# Sheet1.net
KiCad netlist of a schematic drawn in Altium Designer
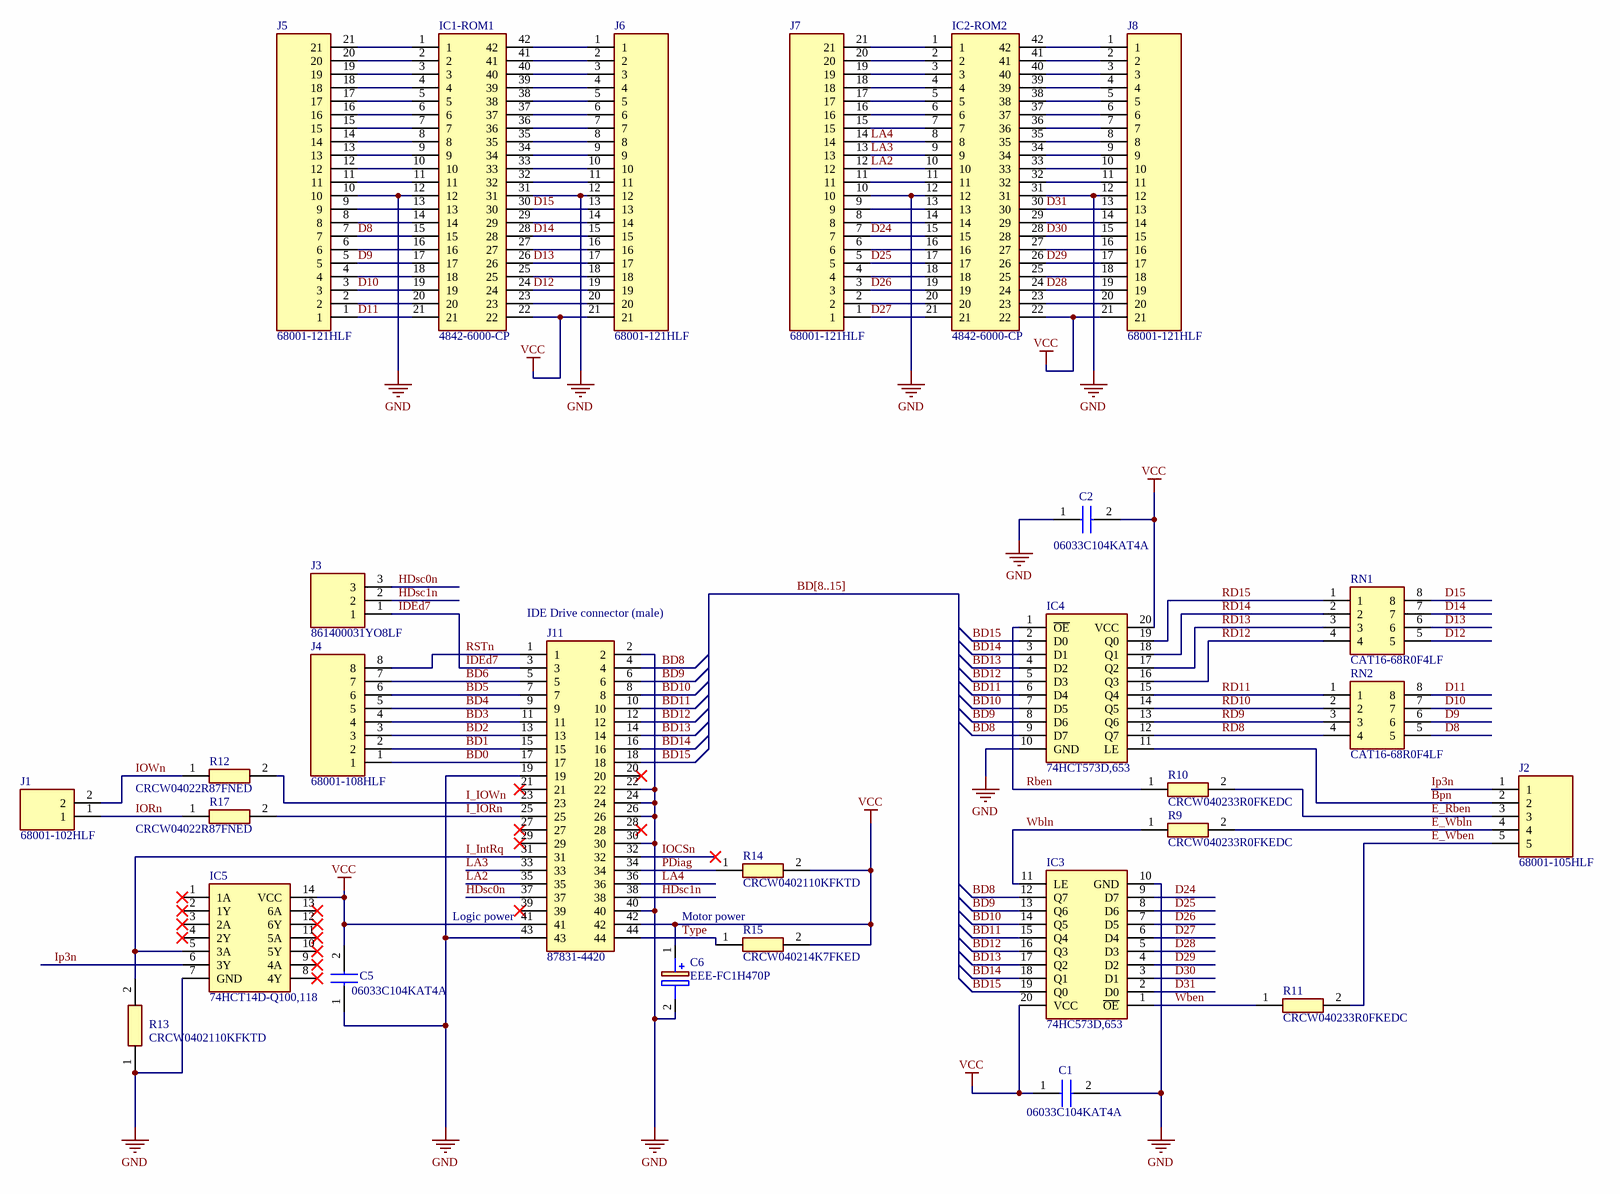
[diagram p0: Sheet1.SchDoc]

(export (version "E")
  (design (tool "Eeschema 10.0.6"))
  (components
    (comp (ref "C1")
      (value "06033C104KAT4A")
      (footprint "SamacSys:CAPC1608X90N")
      (description "Capacitor")
      (fields (field (name "MOUSER PART NUMBER") "581-06033C104KAT4A"))
      (libsource (lib "*") (part "06033C104KAT4A"))
    )
    (comp (ref "C2")
      (value "06033C104KAT4A")
      (footprint "SamacSys:CAPC1608X90N")
      (description "Capacitor")
      (fields (field (name "MOUSER PART NUMBER") "581-06033C104KAT4A"))
      (libsource (lib "*") (part "06033C104KAT4A"))
    )
    (comp (ref "C5")
      (value "06033C104KAT4A")
      (footprint "SamacSys:CAPC1608X90N")
      (description "Capacitor")
      (fields (field (name "MOUSER PART NUMBER") "581-06033C104KAT4A"))
      (libsource (lib "*") (part "06033C104KAT4A"))
    )
    (comp (ref "C6")
      (value "EEE-FC1H470P")
      (footprint "SamacSys:EEEFK1V331P")
      (description "Capacitor Polarised")
      (fields (field (name "MOUSER PART NUMBER") "667-EEE-FC1H470P"))
      (libsource (lib "*") (part "EEE-FC1H470P"))
    )
    (comp (ref "IC1-ROM1")
      (value "4842-6000-CP")
      (footprint "SamacSys:48426000CP")
      (description "Connector")
      (fields (field (name "MOUSER PART NUMBER") "517-4842-6000-CP"))
      (libsource (lib "*") (part "4842-6000-CP"))
    )
    (comp (ref "IC2-ROM2")
      (value "4842-6000-CP")
      (footprint "SamacSys:48426000CP")
      (description "Connector")
      (fields (field (name "MOUSER PART NUMBER") "517-4842-6000-CP"))
      (libsource (lib "*") (part "4842-6000-CP"))
    )
    (comp (ref "IC3")
      (value "74HC573D,653")
      (footprint "SamacSys:SOIC127P1032X265-20N")
      (description "Integrated Circuit")
      (fields (field (name "MOUSER PART NUMBER") "771-74HC573D-T"))
      (libsource (lib "*") (part "74HC573D,653"))
    )
    (comp (ref "IC4")
      (value "74HCT573D,653")
      (footprint "SamacSys:SOIC127P1032X265-20N")
      (description "Integrated Circuit")
      (fields (field (name "MOUSER PART NUMBER") "771-HCT573D653"))
      (libsource (lib "*") (part "74HCT573D,653"))
    )
    (comp (ref "IC5")
      (value "74HCT14D-Q100,118")
      (footprint "SamacSys:SOIC127P600X175-14N")
      (description "Integrated Circuit")
      (fields (field (name "MOUSER PART NUMBER") "771-74HCT14D-Q100118"))
      (libsource (lib "*") (part "74HCT14D-Q100,118"))
    )
    (comp (ref "J1")
      (value "68001-102HLF")
      (footprint "SamacSys:HDRV2W67P0X254_1X2_508X241X858P")
      (description "Connector")
      (fields (field (name "MOUSER PART NUMBER") "649-68001-102HLF"))
      (libsource (lib "*") (part "68001-102HLF"))
    )
    (comp (ref "J2")
      (value "68001-105HLF")
      (footprint "SamacSys:HDRV5W90P0X254_1X5_1270X241X1143P")
      (description "Connector")
      (fields (field (name "MOUSER PART NUMBER") "649-68001-105HLF"))
      (libsource (lib "*") (part "68001-105HLF"))
    )
    (comp (ref "J3")
      (value "861400031YO8LF")
      (footprint "SamacSys:HDRV3W63P0X254_1X3_762X254X980P")
      (description "Connector")
      (fields (field (name "MOUSER PART NUMBER") "649-861400031YO8LF"))
      (libsource (lib "*") (part "861400031YO8LF"))
    )
    (comp (ref "J4")
      (value "68001-108HLF")
      (footprint "SamacSys:HDRV8W90P0X254_1X8_2032X241X1143P")
      (description "Connector")
      (fields (field (name "MOUSER PART NUMBER") "649-68001-108HLF"))
      (libsource (lib "*") (part "68001-108HLF"))
    )
    (comp (ref "J5")
      (value "68001-121HLF")
      (footprint "SamacSys:HDRV21W67P0X254_1X21_5334X241X858P")
      (description "Connector")
      (fields (field (name "MOUSER PART NUMBER") "649-68001-121HLF"))
      (libsource (lib "*") (part "68001-121HLF"))
    )
    (comp (ref "J6")
      (value "68001-121HLF")
      (footprint "SamacSys:HDRV21W67P0X254_1X21_5334X241X858P")
      (description "Connector")
      (fields (field (name "MOUSER PART NUMBER") "649-68001-121HLF"))
      (libsource (lib "") (part "68001-121HLF_1"))
    )
    (comp (ref "J7")
      (value "68001-121HLF")
      (footprint "SamacSys:HDRV21W67P0X254_1X21_5334X241X858P")
      (description "Connector")
      (fields (field (name "MOUSER PART NUMBER") "649-68001-121HLF"))
      (libsource (lib "*") (part "68001-121HLF"))
    )
    (comp (ref "J8")
      (value "68001-121HLF")
      (footprint "SamacSys:HDRV21W67P0X254_1X21_5334X241X858P")
      (description "Connector")
      (fields (field (name "MOUSER PART NUMBER") "649-68001-121HLF"))
      (libsource (lib "") (part "68001-121HLF_1"))
    )
    (comp (ref "J11")
      (value "87831-4420")
      (footprint "SamacSys:SHDR44W55P200_2X22_4665X630X640P")
      (description "Connector")
      (fields (field (name "MOUSER PART NUMBER") "538-87831-4420"))
      (libsource (lib "*") (part "87831-4420"))
    )
    (comp (ref "R9")
      (value "CRCW040233R0FKEDC")
      (footprint "SamacSys:RESC1005X35N")
      (description "Resistor")
      (fields (field (name "MOUSER PART NUMBER") "71-CRCW040233R0FKEDC"))
      (libsource (lib "*") (part "CRCW040233R0FKEDC"))
    )
    (comp (ref "R10")
      (value "CRCW040233R0FKEDC")
      (footprint "SamacSys:RESC1005X35N")
      (description "Resistor")
      (fields (field (name "MOUSER PART NUMBER") "71-CRCW040233R0FKEDC"))
      (libsource (lib "*") (part "CRCW040233R0FKEDC"))
    )
    (comp (ref "R11")
      (value "CRCW040233R0FKEDC")
      (footprint "SamacSys:RESC1005X35N")
      (description "Resistor")
      (fields (field (name "MOUSER PART NUMBER") "71-CRCW040233R0FKEDC"))
      (libsource (lib "*") (part "CRCW040233R0FKEDC"))
    )
    (comp (ref "R12")
      (value "CRCW04022R87FNED")
      (footprint "SamacSys:RESC1005X40N")
      (description "Resistor")
      (fields (field (name "MOUSER PART NUMBER") "71-CRCW04022R87FNED"))
      (libsource (lib "*") (part "CRCW04022R87FNED"))
    )
    (comp (ref "R13")
      (value "CRCW0402110KFKTD")
      (footprint "SamacSys:RESC1005X40N")
      (description "Resistor")
      (fields (field (name "MOUSER PART NUMBER") "71-CRCW0402-110K"))
      (libsource (lib "") (part "CRCW0402110KFKTD_1"))
    )
    (comp (ref "R14")
      (value "CRCW0402110KFKTD")
      (footprint "SamacSys:RESC1005X40N")
      (description "Resistor")
      (fields (field (name "MOUSER PART NUMBER") "71-CRCW0402-110K"))
      (libsource (lib "*") (part "CRCW0402110KFKTD"))
    )
    (comp (ref "R15")
      (value "CRCW040214K7FKED")
      (footprint "SamacSys:RESC1005X40N")
      (description "Resistor")
      (fields (field (name "MOUSER PART NUMBER") "71-CRCW0402-14.7K-E3"))
      (libsource (lib "*") (part "CRCW040214K7FKED"))
    )
    (comp (ref "R17")
      (value "CRCW04022R87FNED")
      (footprint "SamacSys:RESC1005X40N")
      (description "Resistor")
      (fields (field (name "MOUSER PART NUMBER") "71-CRCW04022R87FNED"))
      (libsource (lib "*") (part "CRCW04022R87FNED"))
    )
    (comp (ref "RN1")
      (value "CAT16-68R0F4LF")
      (footprint "SamacSys:CAT1668R0F4LF")
      (description "Resistor Network")
      (fields (field (name "MOUSER PART NUMBER") "652-CAT16-68R0F4LF"))
      (libsource (lib "*") (part "CAT16-68R0F4LF"))
    )
    (comp (ref "RN2")
      (value "CAT16-68R0F4LF")
      (footprint "SamacSys:CAT1668R0F4LF")
      (description "Resistor Network")
      (fields (field (name "MOUSER PART NUMBER") "652-CAT16-68R0F4LF"))
      (libsource (lib "*") (part "CAT16-68R0F4LF"))
    )
  )
  (nets
    (net (code "1") (name "/BD0") (class "Default")
      (node (ref "J11") (pin "17") (pinfunction "17_17") (pintype "passive"))
      (node (ref "J4") (pin "1") (pinfunction "1_1") (pintype "passive"))
    )
    (net (code "2") (name "/BD1") (class "Default")
      (node (ref "J11") (pin "15") (pinfunction "15_15") (pintype "passive"))
      (node (ref "J4") (pin "2") (pinfunction "2_2") (pintype "passive"))
    )
    (net (code "3") (name "/BD2") (class "Default")
      (node (ref "J11") (pin "13") (pinfunction "13_13") (pintype "passive"))
      (node (ref "J4") (pin "3") (pinfunction "3_3") (pintype "passive"))
    )
    (net (code "4") (name "/BD3") (class "Default")
      (node (ref "J11") (pin "11") (pinfunction "11_11") (pintype "passive"))
      (node (ref "J4") (pin "4") (pinfunction "4_4") (pintype "passive"))
    )
    (net (code "5") (name "/BD4") (class "Default")
      (node (ref "J11") (pin "9") (pinfunction "9_9") (pintype "passive"))
      (node (ref "J4") (pin "5") (pinfunction "5_5") (pintype "passive"))
    )
    (net (code "6") (name "/BD5") (class "Default")
      (node (ref "J11") (pin "7") (pinfunction "7_7") (pintype "passive"))
      (node (ref "J4") (pin "6") (pinfunction "6_6") (pintype "passive"))
    )
    (net (code "7") (name "/BD6") (class "Default")
      (node (ref "J11") (pin "5") (pinfunction "5_5") (pintype "passive"))
      (node (ref "J4") (pin "7") (pinfunction "7_7") (pintype "passive"))
    )
    (net (code "8") (name "/BD8") (class "Default")
      (node (ref "IC3") (pin "12") (pinfunction "Q7_12") (pintype "passive"))
      (node (ref "IC4") (pin "9") (pinfunction "D7_9") (pintype "passive"))
      (node (ref "J11") (pin "4") (pinfunction "4_4") (pintype "passive"))
    )
    (net (code "9") (name "/BD9") (class "Default")
      (node (ref "IC3") (pin "13") (pinfunction "Q6_13") (pintype "passive"))
      (node (ref "IC4") (pin "8") (pinfunction "D6_8") (pintype "passive"))
      (node (ref "J11") (pin "6") (pinfunction "6_6") (pintype "passive"))
    )
    (net (code "10") (name "/BD10") (class "Default")
      (node (ref "IC3") (pin "14") (pinfunction "Q5_14") (pintype "passive"))
      (node (ref "IC4") (pin "7") (pinfunction "D5_7") (pintype "passive"))
      (node (ref "J11") (pin "8") (pinfunction "8_8") (pintype "passive"))
    )
    (net (code "11") (name "/BD11") (class "Default")
      (node (ref "IC3") (pin "15") (pinfunction "Q4_15") (pintype "passive"))
      (node (ref "IC4") (pin "6") (pinfunction "D4_6") (pintype "passive"))
      (node (ref "J11") (pin "10") (pinfunction "10_10") (pintype "passive"))
    )
    (net (code "12") (name "/BD12") (class "Default")
      (node (ref "IC3") (pin "16") (pinfunction "Q3_16") (pintype "passive"))
      (node (ref "IC4") (pin "5") (pinfunction "D3_5") (pintype "passive"))
      (node (ref "J11") (pin "12") (pinfunction "12_12") (pintype "passive"))
    )
    (net (code "13") (name "/BD13") (class "Default")
      (node (ref "IC3") (pin "17") (pinfunction "Q2_17") (pintype "passive"))
      (node (ref "IC4") (pin "4") (pinfunction "D2_4") (pintype "passive"))
      (node (ref "J11") (pin "14") (pinfunction "14_14") (pintype "passive"))
    )
    (net (code "14") (name "/BD14") (class "Default")
      (node (ref "IC3") (pin "18") (pinfunction "Q1_18") (pintype "passive"))
      (node (ref "IC4") (pin "3") (pinfunction "D1_3") (pintype "passive"))
      (node (ref "J11") (pin "16") (pinfunction "16_16") (pintype "passive"))
    )
    (net (code "15") (name "/BD15") (class "Default")
      (node (ref "IC3") (pin "19") (pinfunction "Q0_19") (pintype "passive"))
      (node (ref "IC4") (pin "2") (pinfunction "D0_2") (pintype "passive"))
      (node (ref "J11") (pin "18") (pinfunction "18_18") (pintype "passive"))
    )
    (net (code "17") (name "/Bpn") (class "Default")
      (node (ref "IC4") (pin "11") (pinfunction "LE_11") (pintype "passive"))
      (node (ref "J2") (pin "2") (pinfunction "2_2") (pintype "passive"))
    )
    (net (code "18") (name "/D8") (class "Default")
      (node (ref "IC1-ROM1") (pin "15") (pinfunction "15_15") (pintype "passive"))
      (node (ref "J5") (pin "7") (pinfunction "7_7") (pintype "passive"))
      (node (ref "RN2") (pin "5") (pinfunction "5_5") (pintype "passive"))
    )
    (net (code "19") (name "/D9") (class "Default")
      (node (ref "IC1-ROM1") (pin "17") (pinfunction "17_17") (pintype "passive"))
      (node (ref "J5") (pin "5") (pinfunction "5_5") (pintype "passive"))
      (node (ref "RN2") (pin "6") (pinfunction "6_6") (pintype "passive"))
    )
    (net (code "20") (name "/D10") (class "Default")
      (node (ref "IC1-ROM1") (pin "19") (pinfunction "19_19") (pintype "passive"))
      (node (ref "J5") (pin "3") (pinfunction "3_3") (pintype "passive"))
      (node (ref "RN2") (pin "7") (pinfunction "7_7") (pintype "passive"))
    )
    (net (code "21") (name "/D11") (class "Default")
      (node (ref "IC1-ROM1") (pin "21") (pinfunction "21_21") (pintype "passive"))
      (node (ref "J5") (pin "1") (pinfunction "1_1") (pintype "passive"))
      (node (ref "RN2") (pin "8") (pinfunction "8_8") (pintype "passive"))
    )
    (net (code "22") (name "/D12") (class "Default")
      (node (ref "IC1-ROM1") (pin "24") (pinfunction "24_24") (pintype "passive"))
      (node (ref "J6") (pin "19") (pinfunction "19_19") (pintype "passive"))
      (node (ref "RN1") (pin "5") (pinfunction "5_5") (pintype "passive"))
    )
    (net (code "23") (name "/D13") (class "Default")
      (node (ref "IC1-ROM1") (pin "26") (pinfunction "26_26") (pintype "passive"))
      (node (ref "J6") (pin "17") (pinfunction "17_17") (pintype "passive"))
      (node (ref "RN1") (pin "6") (pinfunction "6_6") (pintype "passive"))
    )
    (net (code "24") (name "/D14") (class "Default")
      (node (ref "IC1-ROM1") (pin "28") (pinfunction "28_28") (pintype "passive"))
      (node (ref "J6") (pin "15") (pinfunction "15_15") (pintype "passive"))
      (node (ref "RN1") (pin "7") (pinfunction "7_7") (pintype "passive"))
    )
    (net (code "25") (name "/D15") (class "Default")
      (node (ref "IC1-ROM1") (pin "30") (pinfunction "30_30") (pintype "passive"))
      (node (ref "J6") (pin "13") (pinfunction "13_13") (pintype "passive"))
      (node (ref "RN1") (pin "8") (pinfunction "8_8") (pintype "passive"))
    )
    (net (code "26") (name "/D24") (class "Default")
      (node (ref "IC2-ROM2") (pin "15") (pinfunction "15_15") (pintype "passive"))
      (node (ref "IC3") (pin "9") (pinfunction "D7_9") (pintype "passive"))
      (node (ref "J7") (pin "7") (pinfunction "7_7") (pintype "passive"))
    )
    (net (code "27") (name "/D25") (class "Default")
      (node (ref "IC2-ROM2") (pin "17") (pinfunction "17_17") (pintype "passive"))
      (node (ref "IC3") (pin "8") (pinfunction "D6_8") (pintype "passive"))
      (node (ref "J7") (pin "5") (pinfunction "5_5") (pintype "passive"))
    )
    (net (code "28") (name "/D26") (class "Default")
      (node (ref "IC2-ROM2") (pin "19") (pinfunction "19_19") (pintype "passive"))
      (node (ref "IC3") (pin "7") (pinfunction "D5_7") (pintype "passive"))
      (node (ref "J7") (pin "3") (pinfunction "3_3") (pintype "passive"))
    )
    (net (code "29") (name "/D27") (class "Default")
      (node (ref "IC2-ROM2") (pin "21") (pinfunction "21_21") (pintype "passive"))
      (node (ref "IC3") (pin "6") (pinfunction "D4_6") (pintype "passive"))
      (node (ref "J7") (pin "1") (pinfunction "1_1") (pintype "passive"))
    )
    (net (code "30") (name "/D28") (class "Default")
      (node (ref "IC2-ROM2") (pin "24") (pinfunction "24_24") (pintype "passive"))
      (node (ref "IC3") (pin "5") (pinfunction "D3_5") (pintype "passive"))
      (node (ref "J8") (pin "19") (pinfunction "19_19") (pintype "passive"))
    )
    (net (code "31") (name "/D29") (class "Default")
      (node (ref "IC2-ROM2") (pin "26") (pinfunction "26_26") (pintype "passive"))
      (node (ref "IC3") (pin "4") (pinfunction "D2_4") (pintype "passive"))
      (node (ref "J8") (pin "17") (pinfunction "17_17") (pintype "passive"))
    )
    (net (code "32") (name "/D30") (class "Default")
      (node (ref "IC2-ROM2") (pin "28") (pinfunction "28_28") (pintype "passive"))
      (node (ref "IC3") (pin "3") (pinfunction "D1_3") (pintype "passive"))
      (node (ref "J8") (pin "15") (pinfunction "15_15") (pintype "passive"))
    )
    (net (code "33") (name "/D31") (class "Default")
      (node (ref "IC2-ROM2") (pin "30") (pinfunction "30_30") (pintype "passive"))
      (node (ref "IC3") (pin "2") (pinfunction "D0_2") (pintype "passive"))
      (node (ref "J8") (pin "13") (pinfunction "13_13") (pintype "passive"))
    )
    (net (code "34") (name "/E_Rben") (class "Default")
      (node (ref "J2") (pin "3") (pinfunction "3_3") (pintype "passive"))
      (node (ref "R10") (pin "2") (pinfunction "2_2") (pintype "passive"))
    )
    (net (code "35") (name "/E_Wben") (class "Default")
      (node (ref "J2") (pin "5") (pinfunction "5_5") (pintype "passive"))
      (node (ref "R11") (pin "2") (pinfunction "2_2") (pintype "passive"))
    )
    (net (code "36") (name "/E_Wbln") (class "Default")
      (node (ref "J2") (pin "4") (pinfunction "4_4") (pintype "passive"))
      (node (ref "R9") (pin "2") (pinfunction "2_2") (pintype "passive"))
    )
    (net (code "37") (name "/HDsc0n") (class "Default")
      (node (ref "J11") (pin "37") (pinfunction "37_37") (pintype "passive"))
      (node (ref "J3") (pin "3") (pinfunction "3_3") (pintype "passive"))
    )
    (net (code "38") (name "/HDsc1n") (class "Default")
      (node (ref "J11") (pin "38") (pinfunction "38_38") (pintype "passive"))
      (node (ref "J3") (pin "2") (pinfunction "2_2") (pintype "passive"))
    )
    (net (code "39") (name "/IDEd7") (class "Default")
      (node (ref "J11") (pin "3") (pinfunction "3_3") (pintype "passive"))
      (node (ref "J3") (pin "1") (pinfunction "1_1") (pintype "passive"))
    )
    (net (code "40") (name "/IOCSn") (class "Default")
      (node (ref "J11") (pin "32") (pinfunction "32_32") (pintype "passive+no_connect"))
    )
    (net (code "41") (name "/IORn") (class "Default")
      (node (ref "J1") (pin "1") (pinfunction "1_1") (pintype "passive"))
      (node (ref "R17") (pin "1") (pinfunction "1_1") (pintype "passive"))
    )
    (net (code "42") (name "/IOWn") (class "Default")
      (node (ref "J1") (pin "2") (pinfunction "2_2") (pintype "passive"))
      (node (ref "R12") (pin "1") (pinfunction "1_1") (pintype "passive"))
    )
    (net (code "43") (name "/I_IORn") (class "Default")
      (node (ref "J11") (pin "25") (pinfunction "25_25") (pintype "passive"))
      (node (ref "R17") (pin "2") (pinfunction "2_2") (pintype "passive"))
    )
    (net (code "44") (name "/I_IOWn") (class "Default")
      (node (ref "J11") (pin "23") (pinfunction "23_23") (pintype "passive"))
      (node (ref "R12") (pin "2") (pinfunction "2_2") (pintype "passive"))
    )
    (net (code "45") (name "/I_IntRq") (class "Default")
      (node (ref "IC5") (pin "5") (pinfunction "3A_5") (pintype "passive"))
      (node (ref "J11") (pin "31") (pinfunction "31_31") (pintype "passive"))
      (node (ref "R13") (pin "2") (pinfunction "2_2") (pintype "passive"))
    )
    (net (code "46") (name "/Ip3n") (class "Default")
      (node (ref "IC5") (pin "6") (pinfunction "3Y_6") (pintype "passive"))
      (node (ref "J2") (pin "1") (pinfunction "1_1") (pintype "passive"))
    )
    (net (code "47") (name "/LA2") (class "Default")
      (node (ref "IC2-ROM2") (pin "10") (pinfunction "10_10") (pintype "passive"))
      (node (ref "J11") (pin "35") (pinfunction "35_35") (pintype "passive"))
      (node (ref "J7") (pin "12") (pinfunction "12_12") (pintype "passive"))
    )
    (net (code "48") (name "/LA3") (class "Default")
      (node (ref "IC2-ROM2") (pin "9") (pinfunction "9_9") (pintype "passive"))
      (node (ref "J11") (pin "33") (pinfunction "33_33") (pintype "passive"))
      (node (ref "J7") (pin "13") (pinfunction "13_13") (pintype "passive"))
    )
    (net (code "49") (name "/LA4") (class "Default")
      (node (ref "IC2-ROM2") (pin "8") (pinfunction "8_8") (pintype "passive"))
      (node (ref "J11") (pin "36") (pinfunction "36_36") (pintype "passive"))
      (node (ref "J7") (pin "14") (pinfunction "14_14") (pintype "passive"))
    )
    (net (code "50") (name "/PDiag") (class "Default")
      (node (ref "J11") (pin "34") (pinfunction "34_34") (pintype "passive"))
      (node (ref "R14") (pin "1") (pinfunction "1_1") (pintype "passive"))
    )
    (net (code "51") (name "/RD8") (class "Default")
      (node (ref "IC4") (pin "12") (pinfunction "Q7_12") (pintype "passive"))
      (node (ref "RN2") (pin "4") (pinfunction "4_4") (pintype "passive"))
    )
    (net (code "52") (name "/RD9") (class "Default")
      (node (ref "IC4") (pin "13") (pinfunction "Q6_13") (pintype "passive"))
      (node (ref "RN2") (pin "3") (pinfunction "3_3") (pintype "passive"))
    )
    (net (code "53") (name "/RD10") (class "Default")
      (node (ref "IC4") (pin "14") (pinfunction "Q5_14") (pintype "passive"))
      (node (ref "RN2") (pin "2") (pinfunction "2_2") (pintype "passive"))
    )
    (net (code "54") (name "/RD11") (class "Default")
      (node (ref "IC4") (pin "15") (pinfunction "Q4_15") (pintype "passive"))
      (node (ref "RN2") (pin "1") (pinfunction "1_1") (pintype "passive"))
    )
    (net (code "55") (name "/RD12") (class "Default")
      (node (ref "IC4") (pin "16") (pinfunction "Q3_16") (pintype "passive"))
      (node (ref "RN1") (pin "4") (pinfunction "4_4") (pintype "passive"))
    )
    (net (code "56") (name "/RD13") (class "Default")
      (node (ref "IC4") (pin "17") (pinfunction "Q2_17") (pintype "passive"))
      (node (ref "RN1") (pin "3") (pinfunction "3_3") (pintype "passive"))
    )
    (net (code "57") (name "/RD14") (class "Default")
      (node (ref "IC4") (pin "18") (pinfunction "Q1_18") (pintype "passive"))
      (node (ref "RN1") (pin "2") (pinfunction "2_2") (pintype "passive"))
    )
    (net (code "58") (name "/RD15") (class "Default")
      (node (ref "IC4") (pin "19") (pinfunction "Q0_19") (pintype "passive"))
      (node (ref "RN1") (pin "1") (pinfunction "1_1") (pintype "passive"))
    )
    (net (code "59") (name "/RSTn") (class "Default")
      (node (ref "J11") (pin "1") (pinfunction "1_1") (pintype "passive"))
      (node (ref "J4") (pin "8") (pinfunction "8_8") (pintype "passive"))
    )
    (net (code "60") (name "/Rben") (class "Default")
      (node (ref "IC4") (pin "1") (pinfunction "~{OE}_1") (pintype "passive"))
      (node (ref "R10") (pin "1") (pinfunction "1_1") (pintype "passive"))
    )
    (net (code "61") (name "/Type") (class "Default")
      (node (ref "J11") (pin "44") (pinfunction "44_44") (pintype "passive"))
      (node (ref "R15") (pin "1") (pinfunction "1_1") (pintype "passive"))
    )
    (net (code "62") (name "/Wben") (class "Default")
      (node (ref "IC3") (pin "1") (pinfunction "~{OE}_1") (pintype "passive"))
      (node (ref "R11") (pin "1") (pinfunction "1_1") (pintype "passive"))
    )
    (net (code "63") (name "/Wbln") (class "Default")
      (node (ref "IC3") (pin "11") (pinfunction "LE_11") (pintype "passive"))
      (node (ref "R9") (pin "1") (pinfunction "1_1") (pintype "passive"))
    )
    (net (code "64") (name "GND") (class "Default")
      (node (ref "C1") (pin "2") (pinfunction "2_2") (pintype "passive"))
      (node (ref "C2") (pin "1") (pinfunction "1_1") (pintype "passive"))
      (node (ref "C5") (pin "1") (pinfunction "1_1") (pintype "passive"))
      (node (ref "C6") (pin "2") (pinfunction "-_2") (pintype "passive"))
      (node (ref "IC1-ROM1") (pin "12") (pinfunction "12_12") (pintype "passive"))
      (node (ref "IC1-ROM1") (pin "31") (pinfunction "31_31") (pintype "passive"))
      (node (ref "IC2-ROM2") (pin "12") (pinfunction "12_12") (pintype "passive"))
      (node (ref "IC2-ROM2") (pin "31") (pinfunction "31_31") (pintype "passive"))
      (node (ref "IC3") (pin "10") (pinfunction "GND_10") (pintype "passive"))
      (node (ref "IC4") (pin "10") (pinfunction "GND_10") (pintype "passive"))
      (node (ref "IC5") (pin "7") (pinfunction "GND_7") (pintype "passive"))
      (node (ref "J11") (pin "19") (pinfunction "19_19") (pintype "passive"))
      (node (ref "J11") (pin "2") (pinfunction "2_2") (pintype "passive"))
      (node (ref "J11") (pin "22") (pinfunction "22_22") (pintype "passive"))
      (node (ref "J11") (pin "24") (pinfunction "24_24") (pintype "passive"))
      (node (ref "J11") (pin "26") (pinfunction "26_26") (pintype "passive"))
      (node (ref "J11") (pin "30") (pinfunction "30_30") (pintype "passive"))
      (node (ref "J11") (pin "40") (pinfunction "40_40") (pintype "passive"))
      (node (ref "J11") (pin "43") (pinfunction "43_43") (pintype "passive"))
      (node (ref "J5") (pin "10") (pinfunction "10_10") (pintype "passive"))
      (node (ref "J6") (pin "12") (pinfunction "12_12") (pintype "passive"))
      (node (ref "J7") (pin "10") (pinfunction "10_10") (pintype "passive"))
      (node (ref "J8") (pin "12") (pinfunction "12_12") (pintype "passive"))
      (node (ref "R13") (pin "1") (pinfunction "1_1") (pintype "passive"))
    )
    (net (code "65") (name "Net-(IC1-ROM1-Pad1)") (class "Default")
      (node (ref "IC1-ROM1") (pin "1") (pinfunction "1_1") (pintype "passive"))
      (node (ref "J5") (pin "21") (pinfunction "21_21") (pintype "passive"))
    )
    (net (code "66") (name "Net-(IC1-ROM1-Pad2)") (class "Default")
      (node (ref "IC1-ROM1") (pin "2") (pinfunction "2_2") (pintype "passive"))
      (node (ref "J5") (pin "20") (pinfunction "20_20") (pintype "passive"))
    )
    (net (code "67") (name "Net-(IC1-ROM1-Pad3)") (class "Default")
      (node (ref "IC1-ROM1") (pin "3") (pinfunction "3_3") (pintype "passive"))
      (node (ref "J5") (pin "19") (pinfunction "19_19") (pintype "passive"))
    )
    (net (code "68") (name "Net-(IC1-ROM1-Pad4)") (class "Default")
      (node (ref "IC1-ROM1") (pin "4") (pinfunction "4_4") (pintype "passive"))
      (node (ref "J5") (pin "18") (pinfunction "18_18") (pintype "passive"))
    )
    (net (code "69") (name "Net-(IC1-ROM1-Pad5)") (class "Default")
      (node (ref "IC1-ROM1") (pin "5") (pinfunction "5_5") (pintype "passive"))
      (node (ref "J5") (pin "17") (pinfunction "17_17") (pintype "passive"))
    )
    (net (code "70") (name "Net-(IC1-ROM1-Pad6)") (class "Default")
      (node (ref "IC1-ROM1") (pin "6") (pinfunction "6_6") (pintype "passive"))
      (node (ref "J5") (pin "16") (pinfunction "16_16") (pintype "passive"))
    )
    (net (code "71") (name "Net-(IC1-ROM1-Pad7)") (class "Default")
      (node (ref "IC1-ROM1") (pin "7") (pinfunction "7_7") (pintype "passive"))
      (node (ref "J5") (pin "15") (pinfunction "15_15") (pintype "passive"))
    )
    (net (code "72") (name "Net-(IC1-ROM1-Pad8)") (class "Default")
      (node (ref "IC1-ROM1") (pin "8") (pinfunction "8_8") (pintype "passive"))
      (node (ref "J5") (pin "14") (pinfunction "14_14") (pintype "passive"))
    )
    (net (code "73") (name "Net-(IC1-ROM1-Pad9)") (class "Default")
      (node (ref "IC1-ROM1") (pin "9") (pinfunction "9_9") (pintype "passive"))
      (node (ref "J5") (pin "13") (pinfunction "13_13") (pintype "passive"))
    )
    (net (code "74") (name "Net-(IC1-ROM1-Pad10)") (class "Default")
      (node (ref "IC1-ROM1") (pin "10") (pinfunction "10_10") (pintype "passive"))
      (node (ref "J5") (pin "12") (pinfunction "12_12") (pintype "passive"))
    )
    (net (code "75") (name "Net-(IC1-ROM1-Pad11)") (class "Default")
      (node (ref "IC1-ROM1") (pin "11") (pinfunction "11_11") (pintype "passive"))
      (node (ref "J5") (pin "11") (pinfunction "11_11") (pintype "passive"))
    )
    (net (code "76") (name "Net-(IC1-ROM1-Pad13)") (class "Default")
      (node (ref "IC1-ROM1") (pin "13") (pinfunction "13_13") (pintype "passive"))
      (node (ref "J5") (pin "9") (pinfunction "9_9") (pintype "passive"))
    )
    (net (code "77") (name "Net-(IC1-ROM1-Pad14)") (class "Default")
      (node (ref "IC1-ROM1") (pin "14") (pinfunction "14_14") (pintype "passive"))
      (node (ref "J5") (pin "8") (pinfunction "8_8") (pintype "passive"))
    )
    (net (code "78") (name "Net-(IC1-ROM1-Pad16)") (class "Default")
      (node (ref "IC1-ROM1") (pin "16") (pinfunction "16_16") (pintype "passive"))
      (node (ref "J5") (pin "6") (pinfunction "6_6") (pintype "passive"))
    )
    (net (code "79") (name "Net-(IC1-ROM1-Pad18)") (class "Default")
      (node (ref "IC1-ROM1") (pin "18") (pinfunction "18_18") (pintype "passive"))
      (node (ref "J5") (pin "4") (pinfunction "4_4") (pintype "passive"))
    )
    (net (code "80") (name "Net-(IC1-ROM1-Pad20)") (class "Default")
      (node (ref "IC1-ROM1") (pin "20") (pinfunction "20_20") (pintype "passive"))
      (node (ref "J5") (pin "2") (pinfunction "2_2") (pintype "passive"))
    )
    (net (code "81") (name "Net-(IC1-ROM1-Pad23)") (class "Default")
      (node (ref "IC1-ROM1") (pin "23") (pinfunction "23_23") (pintype "passive"))
      (node (ref "J6") (pin "20") (pinfunction "20_20") (pintype "passive"))
    )
    (net (code "82") (name "Net-(IC1-ROM1-Pad25)") (class "Default")
      (node (ref "IC1-ROM1") (pin "25") (pinfunction "25_25") (pintype "passive"))
      (node (ref "J6") (pin "18") (pinfunction "18_18") (pintype "passive"))
    )
    (net (code "83") (name "Net-(IC1-ROM1-Pad27)") (class "Default")
      (node (ref "IC1-ROM1") (pin "27") (pinfunction "27_27") (pintype "passive"))
      (node (ref "J6") (pin "16") (pinfunction "16_16") (pintype "passive"))
    )
    (net (code "84") (name "Net-(IC1-ROM1-Pad29)") (class "Default")
      (node (ref "IC1-ROM1") (pin "29") (pinfunction "29_29") (pintype "passive"))
      (node (ref "J6") (pin "14") (pinfunction "14_14") (pintype "passive"))
    )
    (net (code "85") (name "Net-(IC1-ROM1-Pad32)") (class "Default")
      (node (ref "IC1-ROM1") (pin "32") (pinfunction "32_32") (pintype "passive"))
      (node (ref "J6") (pin "11") (pinfunction "11_11") (pintype "passive"))
    )
    (net (code "86") (name "Net-(IC1-ROM1-Pad33)") (class "Default")
      (node (ref "IC1-ROM1") (pin "33") (pinfunction "33_33") (pintype "passive"))
      (node (ref "J6") (pin "10") (pinfunction "10_10") (pintype "passive"))
    )
    (net (code "87") (name "Net-(IC1-ROM1-Pad34)") (class "Default")
      (node (ref "IC1-ROM1") (pin "34") (pinfunction "34_34") (pintype "passive"))
      (node (ref "J6") (pin "9") (pinfunction "9_9") (pintype "passive"))
    )
    (net (code "88") (name "Net-(IC1-ROM1-Pad35)") (class "Default")
      (node (ref "IC1-ROM1") (pin "35") (pinfunction "35_35") (pintype "passive"))
      (node (ref "J6") (pin "8") (pinfunction "8_8") (pintype "passive"))
    )
    (net (code "89") (name "Net-(IC1-ROM1-Pad36)") (class "Default")
      (node (ref "IC1-ROM1") (pin "36") (pinfunction "36_36") (pintype "passive"))
      (node (ref "J6") (pin "7") (pinfunction "7_7") (pintype "passive"))
    )
    (net (code "90") (name "Net-(IC1-ROM1-Pad37)") (class "Default")
      (node (ref "IC1-ROM1") (pin "37") (pinfunction "37_37") (pintype "passive"))
      (node (ref "J6") (pin "6") (pinfunction "6_6") (pintype "passive"))
    )
    (net (code "91") (name "Net-(IC1-ROM1-Pad38)") (class "Default")
      (node (ref "IC1-ROM1") (pin "38") (pinfunction "38_38") (pintype "passive"))
      (node (ref "J6") (pin "5") (pinfunction "5_5") (pintype "passive"))
    )
    (net (code "92") (name "Net-(IC1-ROM1-Pad39)") (class "Default")
      (node (ref "IC1-ROM1") (pin "39") (pinfunction "39_39") (pintype "passive"))
      (node (ref "J6") (pin "4") (pinfunction "4_4") (pintype "passive"))
    )
    (net (code "93") (name "Net-(IC1-ROM1-Pad40)") (class "Default")
      (node (ref "IC1-ROM1") (pin "40") (pinfunction "40_40") (pintype "passive"))
      (node (ref "J6") (pin "3") (pinfunction "3_3") (pintype "passive"))
    )
    (net (code "94") (name "Net-(IC1-ROM1-Pad41)") (class "Default")
      (node (ref "IC1-ROM1") (pin "41") (pinfunction "41_41") (pintype "passive"))
      (node (ref "J6") (pin "2") (pinfunction "2_2") (pintype "passive"))
    )
    (net (code "95") (name "Net-(IC1-ROM1-Pad42)") (class "Default")
      (node (ref "IC1-ROM1") (pin "42") (pinfunction "42_42") (pintype "passive"))
      (node (ref "J6") (pin "1") (pinfunction "1_1") (pintype "passive"))
    )
    (net (code "96") (name "Net-(IC2-ROM2-Pad1)") (class "Default")
      (node (ref "IC2-ROM2") (pin "1") (pinfunction "1_1") (pintype "passive"))
      (node (ref "J7") (pin "21") (pinfunction "21_21") (pintype "passive"))
    )
    (net (code "97") (name "Net-(IC2-ROM2-Pad2)") (class "Default")
      (node (ref "IC2-ROM2") (pin "2") (pinfunction "2_2") (pintype "passive"))
      (node (ref "J7") (pin "20") (pinfunction "20_20") (pintype "passive"))
    )
    (net (code "98") (name "Net-(IC2-ROM2-Pad3)") (class "Default")
      (node (ref "IC2-ROM2") (pin "3") (pinfunction "3_3") (pintype "passive"))
      (node (ref "J7") (pin "19") (pinfunction "19_19") (pintype "passive"))
    )
    (net (code "99") (name "Net-(IC2-ROM2-Pad4)") (class "Default")
      (node (ref "IC2-ROM2") (pin "4") (pinfunction "4_4") (pintype "passive"))
      (node (ref "J7") (pin "18") (pinfunction "18_18") (pintype "passive"))
    )
    (net (code "100") (name "Net-(IC2-ROM2-Pad5)") (class "Default")
      (node (ref "IC2-ROM2") (pin "5") (pinfunction "5_5") (pintype "passive"))
      (node (ref "J7") (pin "17") (pinfunction "17_17") (pintype "passive"))
    )
    (net (code "101") (name "Net-(IC2-ROM2-Pad6)") (class "Default")
      (node (ref "IC2-ROM2") (pin "6") (pinfunction "6_6") (pintype "passive"))
      (node (ref "J7") (pin "16") (pinfunction "16_16") (pintype "passive"))
    )
    (net (code "102") (name "Net-(IC2-ROM2-Pad7)") (class "Default")
      (node (ref "IC2-ROM2") (pin "7") (pinfunction "7_7") (pintype "passive"))
      (node (ref "J7") (pin "15") (pinfunction "15_15") (pintype "passive"))
    )
    (net (code "103") (name "Net-(IC2-ROM2-Pad11)") (class "Default")
      (node (ref "IC2-ROM2") (pin "11") (pinfunction "11_11") (pintype "passive"))
      (node (ref "J7") (pin "11") (pinfunction "11_11") (pintype "passive"))
    )
    (net (code "104") (name "Net-(IC2-ROM2-Pad13)") (class "Default")
      (node (ref "IC2-ROM2") (pin "13") (pinfunction "13_13") (pintype "passive"))
      (node (ref "J7") (pin "9") (pinfunction "9_9") (pintype "passive"))
    )
    (net (code "105") (name "Net-(IC2-ROM2-Pad14)") (class "Default")
      (node (ref "IC2-ROM2") (pin "14") (pinfunction "14_14") (pintype "passive"))
      (node (ref "J7") (pin "8") (pinfunction "8_8") (pintype "passive"))
    )
    (net (code "106") (name "Net-(IC2-ROM2-Pad16)") (class "Default")
      (node (ref "IC2-ROM2") (pin "16") (pinfunction "16_16") (pintype "passive"))
      (node (ref "J7") (pin "6") (pinfunction "6_6") (pintype "passive"))
    )
    (net (code "107") (name "Net-(IC2-ROM2-Pad18)") (class "Default")
      (node (ref "IC2-ROM2") (pin "18") (pinfunction "18_18") (pintype "passive"))
      (node (ref "J7") (pin "4") (pinfunction "4_4") (pintype "passive"))
    )
    (net (code "108") (name "Net-(IC2-ROM2-Pad20)") (class "Default")
      (node (ref "IC2-ROM2") (pin "20") (pinfunction "20_20") (pintype "passive"))
      (node (ref "J7") (pin "2") (pinfunction "2_2") (pintype "passive"))
    )
    (net (code "109") (name "Net-(IC2-ROM2-Pad23)") (class "Default")
      (node (ref "IC2-ROM2") (pin "23") (pinfunction "23_23") (pintype "passive"))
      (node (ref "J8") (pin "20") (pinfunction "20_20") (pintype "passive"))
    )
    (net (code "110") (name "Net-(IC2-ROM2-Pad25)") (class "Default")
      (node (ref "IC2-ROM2") (pin "25") (pinfunction "25_25") (pintype "passive"))
      (node (ref "J8") (pin "18") (pinfunction "18_18") (pintype "passive"))
    )
    (net (code "111") (name "Net-(IC2-ROM2-Pad27)") (class "Default")
      (node (ref "IC2-ROM2") (pin "27") (pinfunction "27_27") (pintype "passive"))
      (node (ref "J8") (pin "16") (pinfunction "16_16") (pintype "passive"))
    )
    (net (code "112") (name "Net-(IC2-ROM2-Pad29)") (class "Default")
      (node (ref "IC2-ROM2") (pin "29") (pinfunction "29_29") (pintype "passive"))
      (node (ref "J8") (pin "14") (pinfunction "14_14") (pintype "passive"))
    )
    (net (code "113") (name "Net-(IC2-ROM2-Pad32)") (class "Default")
      (node (ref "IC2-ROM2") (pin "32") (pinfunction "32_32") (pintype "passive"))
      (node (ref "J8") (pin "11") (pinfunction "11_11") (pintype "passive"))
    )
    (net (code "114") (name "Net-(IC2-ROM2-Pad33)") (class "Default")
      (node (ref "IC2-ROM2") (pin "33") (pinfunction "33_33") (pintype "passive"))
      (node (ref "J8") (pin "10") (pinfunction "10_10") (pintype "passive"))
    )
    (net (code "115") (name "Net-(IC2-ROM2-Pad34)") (class "Default")
      (node (ref "IC2-ROM2") (pin "34") (pinfunction "34_34") (pintype "passive"))
      (node (ref "J8") (pin "9") (pinfunction "9_9") (pintype "passive"))
    )
    (net (code "116") (name "Net-(IC2-ROM2-Pad35)") (class "Default")
      (node (ref "IC2-ROM2") (pin "35") (pinfunction "35_35") (pintype "passive"))
      (node (ref "J8") (pin "8") (pinfunction "8_8") (pintype "passive"))
    )
    (net (code "117") (name "Net-(IC2-ROM2-Pad36)") (class "Default")
      (node (ref "IC2-ROM2") (pin "36") (pinfunction "36_36") (pintype "passive"))
      (node (ref "J8") (pin "7") (pinfunction "7_7") (pintype "passive"))
    )
    (net (code "118") (name "Net-(IC2-ROM2-Pad37)") (class "Default")
      (node (ref "IC2-ROM2") (pin "37") (pinfunction "37_37") (pintype "passive"))
      (node (ref "J8") (pin "6") (pinfunction "6_6") (pintype "passive"))
    )
    (net (code "119") (name "Net-(IC2-ROM2-Pad38)") (class "Default")
      (node (ref "IC2-ROM2") (pin "38") (pinfunction "38_38") (pintype "passive"))
      (node (ref "J8") (pin "5") (pinfunction "5_5") (pintype "passive"))
    )
    (net (code "120") (name "Net-(IC2-ROM2-Pad39)") (class "Default")
      (node (ref "IC2-ROM2") (pin "39") (pinfunction "39_39") (pintype "passive"))
      (node (ref "J8") (pin "4") (pinfunction "4_4") (pintype "passive"))
    )
    (net (code "121") (name "Net-(IC2-ROM2-Pad40)") (class "Default")
      (node (ref "IC2-ROM2") (pin "40") (pinfunction "40_40") (pintype "passive"))
      (node (ref "J8") (pin "3") (pinfunction "3_3") (pintype "passive"))
    )
    (net (code "122") (name "Net-(IC2-ROM2-Pad41)") (class "Default")
      (node (ref "IC2-ROM2") (pin "41") (pinfunction "41_41") (pintype "passive"))
      (node (ref "J8") (pin "2") (pinfunction "2_2") (pintype "passive"))
    )
    (net (code "123") (name "Net-(IC2-ROM2-Pad42)") (class "Default")
      (node (ref "IC2-ROM2") (pin "42") (pinfunction "42_42") (pintype "passive"))
      (node (ref "J8") (pin "1") (pinfunction "1_1") (pintype "passive"))
    )
    (net (code "124") (name "VCC") (class "Default")
      (node (ref "C1") (pin "1") (pinfunction "1_1") (pintype "passive"))
      (node (ref "C2") (pin "2") (pinfunction "2_2") (pintype "passive"))
      (node (ref "C5") (pin "2") (pinfunction "2_2") (pintype "passive"))
      (node (ref "C6") (pin "1") (pinfunction "+_1") (pintype "passive"))
      (node (ref "IC1-ROM1") (pin "22") (pinfunction "22_22") (pintype "passive"))
      (node (ref "IC2-ROM2") (pin "22") (pinfunction "22_22") (pintype "passive"))
      (node (ref "IC3") (pin "20") (pinfunction "VCC_20") (pintype "passive"))
      (node (ref "IC4") (pin "20") (pinfunction "VCC_20") (pintype "passive"))
      (node (ref "IC5") (pin "14") (pinfunction "VCC_14") (pintype "passive"))
      (node (ref "J11") (pin "41") (pinfunction "41_41") (pintype "passive"))
      (node (ref "J11") (pin "42") (pinfunction "42_42") (pintype "passive"))
      (node (ref "J6") (pin "21") (pinfunction "21_21") (pintype "passive"))
      (node (ref "J8") (pin "21") (pinfunction "21_21") (pintype "passive"))
      (node (ref "R14") (pin "2") (pinfunction "2_2") (pintype "passive"))
      (node (ref "R15") (pin "2") (pinfunction "2_2") (pintype "passive"))
    )
    (net (code "125") (name "unconnected-(IC5-1A-Pad1)") (class "Default")
      (node (ref "IC5") (pin "1") (pinfunction "1A_1") (pintype "passive+no_connect"))
    )
    (net (code "126") (name "unconnected-(IC5-1Y-Pad2)") (class "Default")
      (node (ref "IC5") (pin "2") (pinfunction "1Y_2") (pintype "passive+no_connect"))
    )
    (net (code "127") (name "unconnected-(IC5-2A-Pad3)") (class "Default")
      (node (ref "IC5") (pin "3") (pinfunction "2A_3") (pintype "passive+no_connect"))
    )
    (net (code "128") (name "unconnected-(IC5-2Y-Pad4)") (class "Default")
      (node (ref "IC5") (pin "4") (pinfunction "2Y_4") (pintype "passive+no_connect"))
    )
    (net (code "129") (name "unconnected-(IC5-4A-Pad9)") (class "Default")
      (node (ref "IC5") (pin "9") (pinfunction "4A_9") (pintype "passive+no_connect"))
    )
    (net (code "130") (name "unconnected-(IC5-4Y-Pad8)") (class "Default")
      (node (ref "IC5") (pin "8") (pinfunction "4Y_8") (pintype "passive+no_connect"))
    )
    (net (code "131") (name "unconnected-(IC5-5A-Pad11)") (class "Default")
      (node (ref "IC5") (pin "11") (pinfunction "5A_11") (pintype "passive+no_connect"))
    )
    (net (code "132") (name "unconnected-(IC5-5Y-Pad10)") (class "Default")
      (node (ref "IC5") (pin "10") (pinfunction "5Y_10") (pintype "passive+no_connect"))
    )
    (net (code "133") (name "unconnected-(IC5-6A-Pad13)") (class "Default")
      (node (ref "IC5") (pin "13") (pinfunction "6A_13") (pintype "passive+no_connect"))
    )
    (net (code "134") (name "unconnected-(IC5-6Y-Pad12)") (class "Default")
      (node (ref "IC5") (pin "12") (pinfunction "6Y_12") (pintype "passive+no_connect"))
    )
    (net (code "135") (name "unconnected-(J11-Pad20)") (class "Default")
      (node (ref "J11") (pin "20") (pinfunction "20_20") (pintype "passive+no_connect"))
    )
    (net (code "136") (name "unconnected-(J11-Pad21)") (class "Default")
      (node (ref "J11") (pin "21") (pinfunction "21_21") (pintype "passive+no_connect"))
    )
    (net (code "137") (name "unconnected-(J11-Pad27)") (class "Default")
      (node (ref "J11") (pin "27") (pinfunction "27_27") (pintype "passive+no_connect"))
    )
    (net (code "138") (name "unconnected-(J11-Pad28)") (class "Default")
      (node (ref "J11") (pin "28") (pinfunction "28_28") (pintype "passive+no_connect"))
    )
    (net (code "139") (name "unconnected-(J11-Pad29)") (class "Default")
      (node (ref "J11") (pin "29") (pinfunction "29_29") (pintype "passive+no_connect"))
    )
    (net (code "140") (name "unconnected-(J11-Pad39)") (class "Default")
      (node (ref "J11") (pin "39") (pinfunction "39_39") (pintype "passive+no_connect"))
    )
  )
)
